# 07_Peripheral_Part.net
KiCad netlist of a schematic drawn in Altium Designer
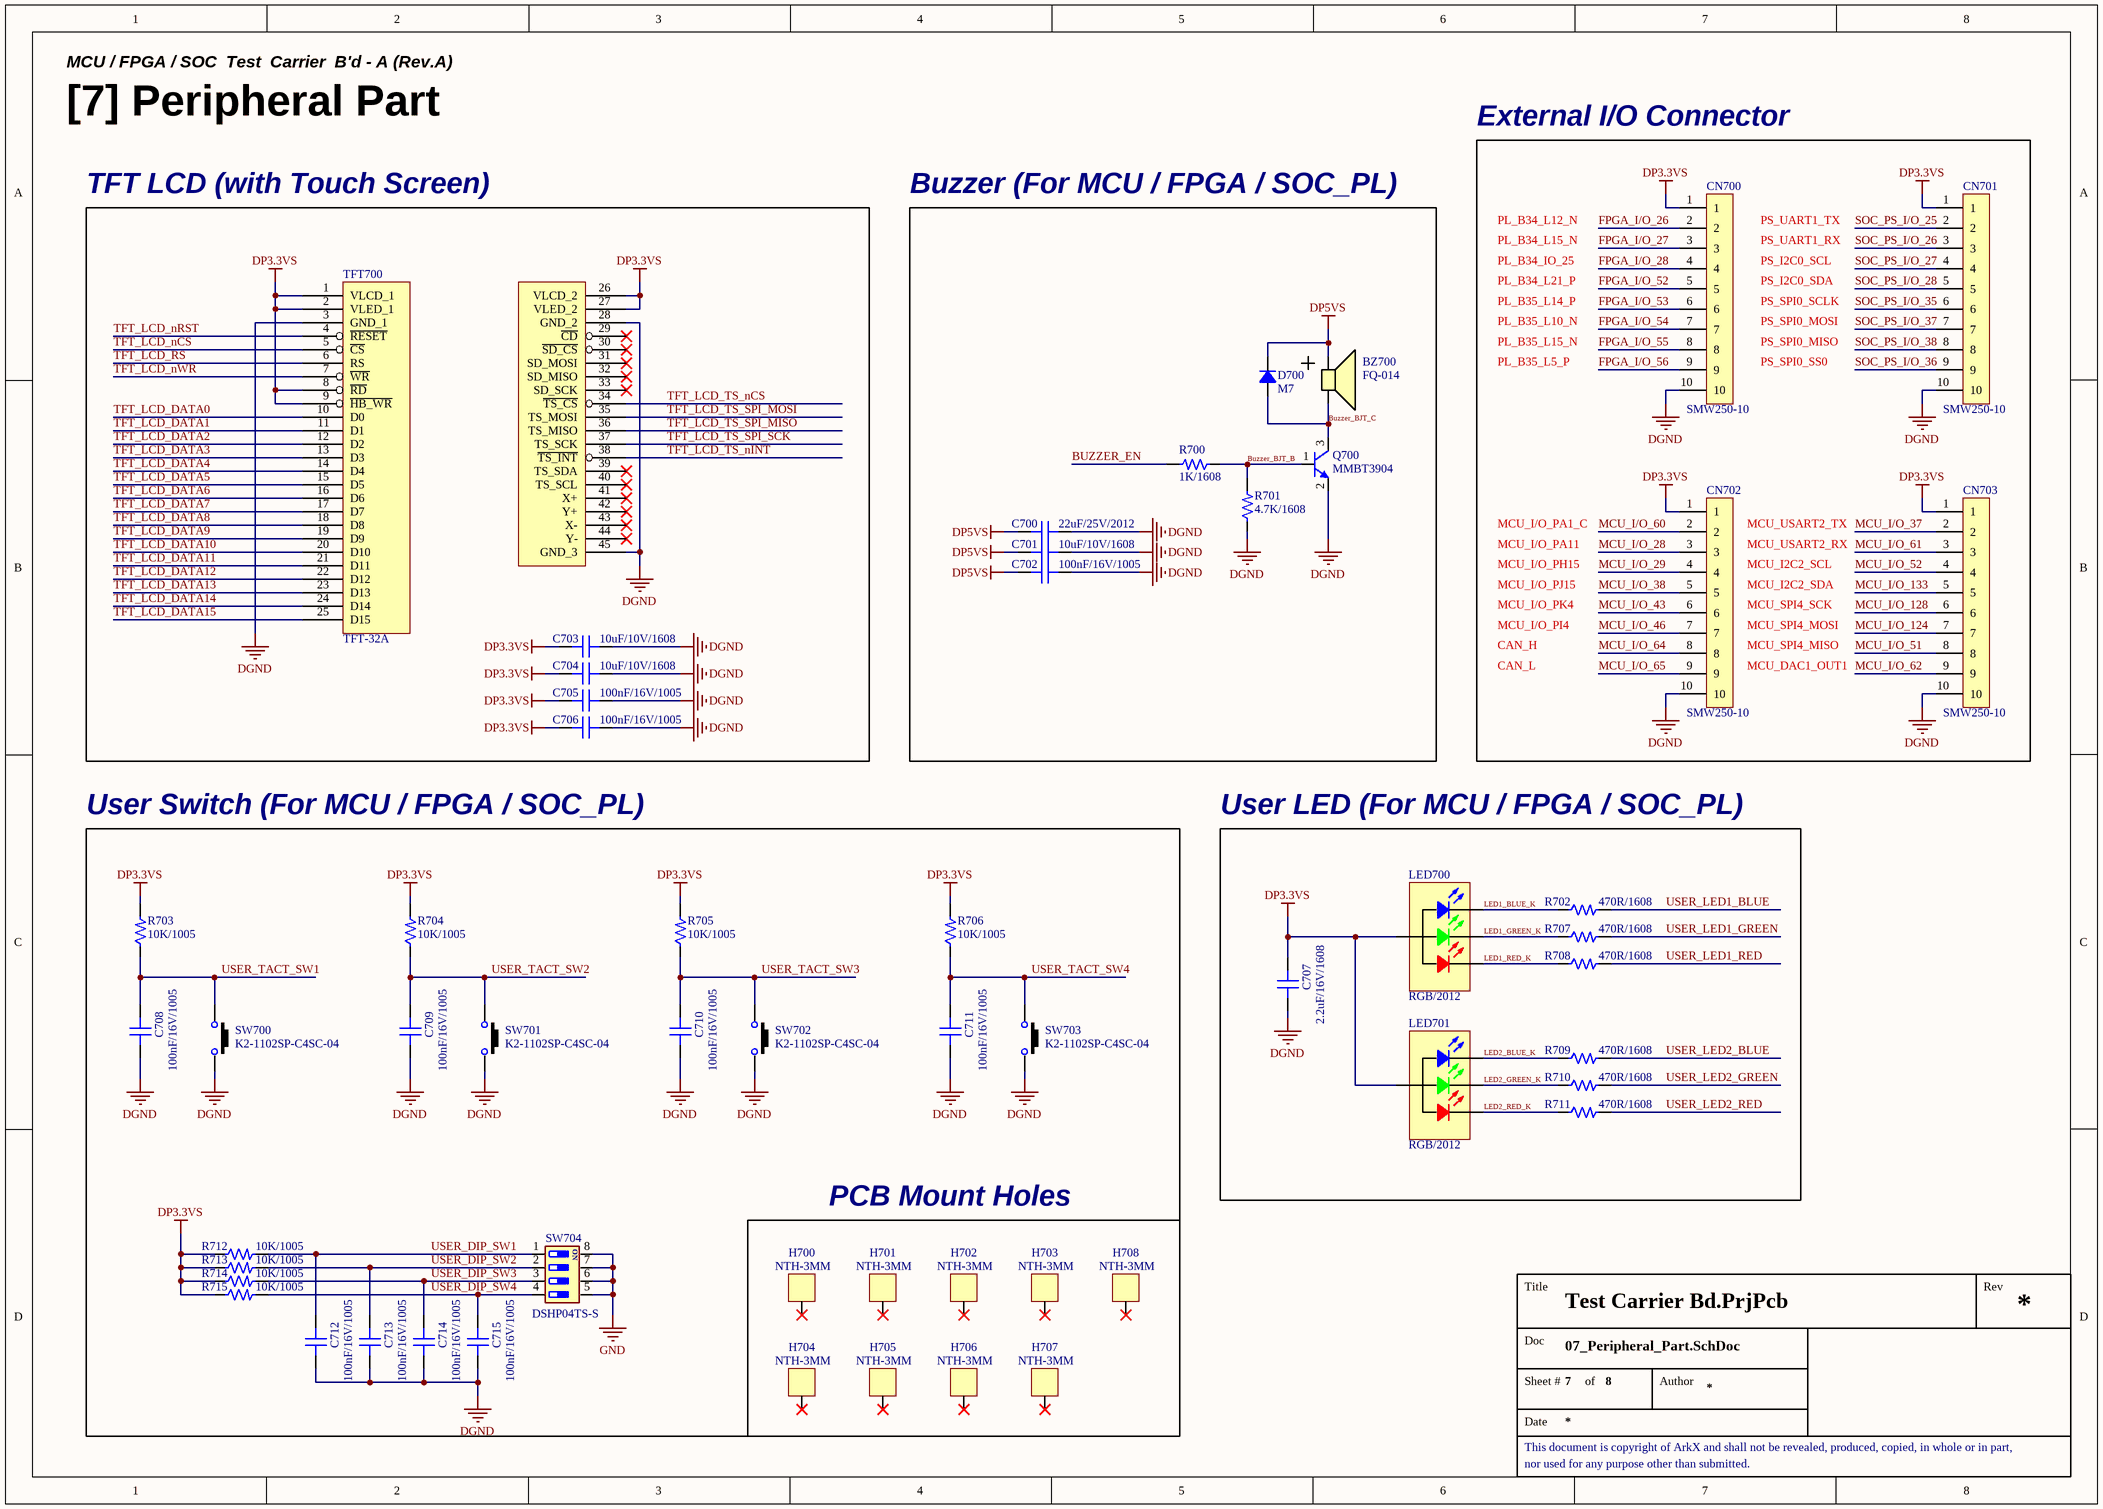
[diagram p0: 07_Peripheral_Part.SchDoc]

(export (version "E")
  (design (tool "Eeschema 10.0.6"))
  (components
    (comp (ref "BZ700")
      (value "FQ-014")
      (footprint "BUZ FQ-013")
      (description "Magnetic Active Buzzer / Rated Voltage: 5V / Size: 9x5.5mm")
      (libsource (lib "Arkx") (part "BZ_FQ-014"))
    )
    (comp (ref "C700")
      (value "22uF/25V/2012")
      (footprint "CAP 2012 (0805_INCH)")
      (description "Ceramic CAP_22uF/25V/2012")
      (fields (field (name "LCSC PART #") "C45783"))
      (libsource (lib "Arkx") (part "CAP_22uF/25V/2012"))
    )
    (comp (ref "C701")
      (value "10uF/10V/1608")
      (footprint "CAP 1608 (0603_INCH)")
      (description "Ceramic CAP_10uF/10V/1608")
      (fields (field (name "LCSC PART #") "C19702"))
      (libsource (lib "Arkx") (part "CAP_10uF/10V/1608"))
    )
    (comp (ref "C702")
      (value "100nF/16V/1005")
      (footprint "CAP 1005 (0402_INCH)")
      (description "Ceramic CAP_100nF/16V/1005")
      (fields (field (name "LCSC PART #") "C1525"))
      (libsource (lib "Arkx") (part "CAP_100nF/16V/1005"))
    )
    (comp (ref "C703")
      (value "10uF/10V/1608")
      (footprint "CAP 1608 (0603_INCH)")
      (description "Ceramic CAP_10uF/10V/1608")
      (fields (field (name "LCSC PART #") "C19702"))
      (libsource (lib "Arkx") (part "CAP_10uF/10V/1608"))
    )
    (comp (ref "C704")
      (value "10uF/10V/1608")
      (footprint "CAP 1608 (0603_INCH)")
      (description "Ceramic CAP_10uF/10V/1608")
      (fields (field (name "LCSC PART #") "C19702"))
      (libsource (lib "Arkx") (part "CAP_10uF/10V/1608"))
    )
    (comp (ref "C705")
      (value "100nF/16V/1005")
      (footprint "CAP 1005 (0402_INCH)")
      (description "Ceramic CAP_100nF/16V/1005")
      (fields (field (name "LCSC PART #") "C1525"))
      (libsource (lib "Arkx") (part "CAP_100nF/16V/1005"))
    )
    (comp (ref "C706")
      (value "100nF/16V/1005")
      (footprint "CAP 1005 (0402_INCH)")
      (description "Ceramic CAP_100nF/16V/1005")
      (fields (field (name "LCSC PART #") "C1525"))
      (libsource (lib "Arkx") (part "CAP_100nF/16V/1005"))
    )
    (comp (ref "C707")
      (value "2.2uF/16V/1608")
      (footprint "CAP 1608 (0603_INCH)")
      (description "Ceramic CAP_2.2uF/16V/1608")
      (fields (field (name "LCSC PART #") "C23630"))
      (libsource (lib "Arkx") (part "CAP_2.2uF/16V/1608"))
    )
    (comp (ref "C708")
      (value "100nF/16V/1005")
      (footprint "CAP 1005 (0402_INCH)")
      (description "Ceramic CAP_100nF/16V/1005")
      (fields (field (name "LCSC PART #") "C1525"))
      (libsource (lib "Arkx") (part "CAP_100nF/16V/1005"))
    )
    (comp (ref "C709")
      (value "100nF/16V/1005")
      (footprint "CAP 1005 (0402_INCH)")
      (description "Ceramic CAP_100nF/16V/1005")
      (fields (field (name "LCSC PART #") "C1525"))
      (libsource (lib "Arkx") (part "CAP_100nF/16V/1005"))
    )
    (comp (ref "C710")
      (value "100nF/16V/1005")
      (footprint "CAP 1005 (0402_INCH)")
      (description "Ceramic CAP_100nF/16V/1005")
      (fields (field (name "LCSC PART #") "C1525"))
      (libsource (lib "Arkx") (part "CAP_100nF/16V/1005"))
    )
    (comp (ref "C711")
      (value "100nF/16V/1005")
      (footprint "CAP 1005 (0402_INCH)")
      (description "Ceramic CAP_100nF/16V/1005")
      (fields (field (name "LCSC PART #") "C1525"))
      (libsource (lib "Arkx") (part "CAP_100nF/16V/1005"))
    )
    (comp (ref "C712")
      (value "100nF/16V/1005")
      (footprint "CAP 1005 (0402_INCH)")
      (description "Ceramic CAP_100nF/16V/1005")
      (fields (field (name "LCSC PART #") "C1525"))
      (libsource (lib "Arkx") (part "CAP_100nF/16V/1005"))
    )
    (comp (ref "C713")
      (value "100nF/16V/1005")
      (footprint "CAP 1005 (0402_INCH)")
      (description "Ceramic CAP_100nF/16V/1005")
      (fields (field (name "LCSC PART #") "C1525"))
      (libsource (lib "Arkx") (part "CAP_100nF/16V/1005"))
    )
    (comp (ref "C714")
      (value "100nF/16V/1005")
      (footprint "CAP 1005 (0402_INCH)")
      (description "Ceramic CAP_100nF/16V/1005")
      (fields (field (name "LCSC PART #") "C1525"))
      (libsource (lib "Arkx") (part "CAP_100nF/16V/1005"))
    )
    (comp (ref "C715")
      (value "100nF/16V/1005")
      (footprint "CAP 1005 (0402_INCH)")
      (description "Ceramic CAP_100nF/16V/1005")
      (fields (field (name "LCSC PART #") "C1525"))
      (libsource (lib "Arkx") (part "CAP_100nF/16V/1005"))
    )
    (comp (ref "CN700")
      (value "SMW250-10")
      (footprint "CON_SMW250-10")
      (description "YEONHO 2.5mm Pitch Vertical Connector 10Pin")
      (libsource (lib "Arkx") (part "CON_SMW250-10"))
    )
    (comp (ref "CN701")
      (value "SMW250-10")
      (footprint "CON_SMW250-10")
      (description "YEONHO 2.5mm Pitch Vertical Connector 10Pin")
      (libsource (lib "Arkx") (part "CON_SMW250-10"))
    )
    (comp (ref "CN702")
      (value "SMW250-10")
      (footprint "CON_SMW250-10")
      (description "YEONHO 2.5mm Pitch Vertical Connector 10Pin")
      (libsource (lib "Arkx") (part "CON_SMW250-10"))
    )
    (comp (ref "CN703")
      (value "SMW250-10")
      (footprint "CON_SMW250-10")
      (description "YEONHO 2.5mm Pitch Vertical Connector 10Pin")
      (libsource (lib "Arkx") (part "CON_SMW250-10"))
    )
    (comp (ref "D700")
      (value "M7")
      (footprint "DIO DO-214AC (SMA)")
      (description "1A 5uA@1kV 1kV 1.1V@1A SMA(DO-214AC)  Diodes - General Purpose ROHS")
      (fields (field (name "LCSC PART #") "C95872"))
      (libsource (lib "Arkx") (part "DIO_M7"))
    )
    (comp (ref "H700")
      (value "NTH-3MM")
      (footprint "HOLE_NTH-3.0MM")
      (description "Non-Through Hole 3mm")
      (libsource (lib "Arkx") (part "HOLE_NTH-3.0MM"))
    )
    (comp (ref "H701")
      (value "NTH-3MM")
      (footprint "HOLE_NTH-3.0MM")
      (description "Non-Through Hole 3mm")
      (libsource (lib "Arkx") (part "HOLE_NTH-3.0MM"))
    )
    (comp (ref "H702")
      (value "NTH-3MM")
      (footprint "HOLE_NTH-3.0MM")
      (description "Non-Through Hole 3mm")
      (libsource (lib "Arkx") (part "HOLE_NTH-3.0MM"))
    )
    (comp (ref "H703")
      (value "NTH-3MM")
      (footprint "HOLE_NTH-3.0MM")
      (description "Non-Through Hole 3mm")
      (libsource (lib "Arkx") (part "HOLE_NTH-3.0MM"))
    )
    (comp (ref "H704")
      (value "NTH-3MM")
      (footprint "HOLE_NTH-3.0MM")
      (description "Non-Through Hole 3mm")
      (libsource (lib "Arkx") (part "HOLE_NTH-3.0MM"))
    )
    (comp (ref "H705")
      (value "NTH-3MM")
      (footprint "HOLE_NTH-3.0MM")
      (description "Non-Through Hole 3mm")
      (libsource (lib "Arkx") (part "HOLE_NTH-3.0MM"))
    )
    (comp (ref "H706")
      (value "NTH-3MM")
      (footprint "HOLE_NTH-3.0MM")
      (description "Non-Through Hole 3mm")
      (libsource (lib "Arkx") (part "HOLE_NTH-3.0MM"))
    )
    (comp (ref "H707")
      (value "NTH-3MM")
      (footprint "HOLE_NTH-3.0MM")
      (description "Non-Through Hole 3mm")
      (libsource (lib "Arkx") (part "HOLE_NTH-3.0MM"))
    )
    (comp (ref "H708")
      (value "NTH-3MM")
      (footprint "HOLE_NTH-3.0MM")
      (description "Non-Through Hole 3mm")
      (libsource (lib "Arkx") (part "HOLE_NTH-3.0MM"))
    )
    (comp (ref "LED700")
      (value "RGB/2012")
      (footprint "LED MHT170RGBCT")
      (fields (field (name "LCSC PART #") "C2962094"))
      (libsource (lib "Arkx") (part "LED_RGB_MHT170RGBCT"))
    )
    (comp (ref "LED701")
      (value "RGB/2012")
      (footprint "LED MHT170RGBCT")
      (fields (field (name "LCSC PART #") "C2962094"))
      (libsource (lib "Arkx") (part "LED_RGB_MHT170RGBCT"))
    )
    (comp (ref "Q700")
      (value "MMBT3904")
      (footprint "SOT 23-3 (DIODES INCORPORATED)")
      (fields (field (name "LCSC PART #") "C20526"))
      (libsource (lib "Arkx") (part "BJT_NPN_MMBT3904"))
    )
    (comp (ref "R700")
      (value "1K/1608")
      (footprint "RES 1608 (0603_inch)")
      (description "RES_1K/1608/0.1W")
      (fields (field (name "LCSC PART #") "C21190"))
      (libsource (lib "Arkx") (part "RES_1K/1608/0.1W"))
    )
    (comp (ref "R701")
      (value "4.7K/1608")
      (footprint "RES 1608 (0603_inch)")
      (description "RES_4.7K/1608/0.1W")
      (fields (field (name "LCSC PART #") "C23162"))
      (libsource (lib "Arkx") (part "RES_4.7K/1608/0.1W"))
    )
    (comp (ref "R702")
      (value "470R/1608")
      (footprint "RES 1608 (0603_inch)")
      (description "RES_470R/1608/0.1W")
      (fields (field (name "LCSC PART #") "C23179"))
      (libsource (lib "Arkx") (part "RES_470R/1608/0.1W"))
    )
    (comp (ref "R703")
      (value "10K/1005")
      (footprint "RES 1005 (0402_inch)")
      (description "RES_10K/1005/62.5mW")
      (fields (field (name "LCSC PART #") "C25744"))
      (libsource (lib "Arkx") (part "RES_10K/1005/62.5mW"))
    )
    (comp (ref "R704")
      (value "10K/1005")
      (footprint "RES 1005 (0402_inch)")
      (description "RES_10K/1005/62.5mW")
      (fields (field (name "LCSC PART #") "C25744"))
      (libsource (lib "Arkx") (part "RES_10K/1005/62.5mW"))
    )
    (comp (ref "R705")
      (value "10K/1005")
      (footprint "RES 1005 (0402_inch)")
      (description "RES_10K/1005/62.5mW")
      (fields (field (name "LCSC PART #") "C25744"))
      (libsource (lib "Arkx") (part "RES_10K/1005/62.5mW"))
    )
    (comp (ref "R706")
      (value "10K/1005")
      (footprint "RES 1005 (0402_inch)")
      (description "RES_10K/1005/62.5mW")
      (fields (field (name "LCSC PART #") "C25744"))
      (libsource (lib "Arkx") (part "RES_10K/1005/62.5mW"))
    )
    (comp (ref "R707")
      (value "470R/1608")
      (footprint "RES 1608 (0603_inch)")
      (description "RES_470R/1608/0.1W")
      (fields (field (name "LCSC PART #") "C23179"))
      (libsource (lib "Arkx") (part "RES_470R/1608/0.1W"))
    )
    (comp (ref "R708")
      (value "470R/1608")
      (footprint "RES 1608 (0603_inch)")
      (description "RES_470R/1608/0.1W")
      (fields (field (name "LCSC PART #") "C23179"))
      (libsource (lib "Arkx") (part "RES_470R/1608/0.1W"))
    )
    (comp (ref "R709")
      (value "470R/1608")
      (footprint "RES 1608 (0603_inch)")
      (description "RES_470R/1608/0.1W")
      (fields (field (name "LCSC PART #") "C23179"))
      (libsource (lib "Arkx") (part "RES_470R/1608/0.1W"))
    )
    (comp (ref "R710")
      (value "470R/1608")
      (footprint "RES 1608 (0603_inch)")
      (description "RES_470R/1608/0.1W")
      (fields (field (name "LCSC PART #") "C23179"))
      (libsource (lib "Arkx") (part "RES_470R/1608/0.1W"))
    )
    (comp (ref "R711")
      (value "470R/1608")
      (footprint "RES 1608 (0603_inch)")
      (description "RES_470R/1608/0.1W")
      (fields (field (name "LCSC PART #") "C23179"))
      (libsource (lib "Arkx") (part "RES_470R/1608/0.1W"))
    )
    (comp (ref "R712")
      (value "10K/1005")
      (footprint "RES 1005 (0402_inch)")
      (description "RES_10K/1005/62.5mW")
      (fields (field (name "LCSC PART #") "C25744"))
      (libsource (lib "Arkx") (part "RES_10K/1005/62.5mW"))
    )
    (comp (ref "R713")
      (value "10K/1005")
      (footprint "RES 1005 (0402_inch)")
      (description "RES_10K/1005/62.5mW")
      (fields (field (name "LCSC PART #") "C25744"))
      (libsource (lib "Arkx") (part "RES_10K/1005/62.5mW"))
    )
    (comp (ref "R714")
      (value "10K/1005")
      (footprint "RES 1005 (0402_inch)")
      (description "RES_10K/1005/62.5mW")
      (fields (field (name "LCSC PART #") "C25744"))
      (libsource (lib "Arkx") (part "RES_10K/1005/62.5mW"))
    )
    (comp (ref "R715")
      (value "10K/1005")
      (footprint "RES 1005 (0402_inch)")
      (description "RES_10K/1005/62.5mW")
      (fields (field (name "LCSC PART #") "C25744"))
      (libsource (lib "Arkx") (part "RES_10K/1005/62.5mW"))
    )
    (comp (ref "SW700")
      (value "K2-1102SP-C4SC-04")
      (footprint "SW K2-1102SP-C4SC-04")
      (fields (field (name "LCSC PART #") "C127509"))
      (libsource (lib "Arkx") (part "SW_K2-1102SP-C4SC-04(2P)"))
    )
    (comp (ref "SW701")
      (value "K2-1102SP-C4SC-04")
      (footprint "SW K2-1102SP-C4SC-04")
      (fields (field (name "LCSC PART #") "C127509"))
      (libsource (lib "Arkx") (part "SW_K2-1102SP-C4SC-04(2P)"))
    )
    (comp (ref "SW702")
      (value "K2-1102SP-C4SC-04")
      (footprint "SW K2-1102SP-C4SC-04")
      (fields (field (name "LCSC PART #") "C127509"))
      (libsource (lib "Arkx") (part "SW_K2-1102SP-C4SC-04(2P)"))
    )
    (comp (ref "SW703")
      (value "K2-1102SP-C4SC-04")
      (footprint "SW K2-1102SP-C4SC-04")
      (fields (field (name "LCSC PART #") "C127509"))
      (libsource (lib "Arkx") (part "SW_K2-1102SP-C4SC-04(2P)"))
    )
    (comp (ref "SW704")
      (value "DSHP04TS-S")
      (footprint "SW_DSHP04TS-S")
      (description "4Bit SPST 24V 25mA Black 3千次 Slide (Standard),凹槽式 SMD-8P,5.4x6.7mm  DIP Switches ROHS")
      (fields (field (name "LCSC PART #") "C319050"))
      (libsource (lib "Arkx") (part "SW_DSHP04TS-S"))
    )
    (comp (ref "TFT700")
      (value "TFT-32A")
      (footprint "LCD_TFT-32A")
      (libsource (lib "Arkx") (part "LCD_TFT-32A"))
    )
  )
  (nets
    (net (code "1") (name "/BUZZER_EN") (class "Default")
      (node (ref "R700") (pin "2") (pinfunction "2_2") (pintype "passive"))
    )
    (net (code "2") (name "/Buzzer_BJT_B") (class "Default")
      (node (ref "Q700") (pin "1") (pinfunction "B_1") (pintype "passive"))
      (node (ref "R700") (pin "1") (pinfunction "1_1") (pintype "passive"))
      (node (ref "R701") (pin "2") (pinfunction "2_2") (pintype "passive"))
    )
    (net (code "3") (name "/Buzzer_BJT_C") (class "Default")
      (node (ref "BZ700") (pin "2") (pinfunction "2_2") (pintype "passive"))
      (node (ref "D700") (pin "1") (pinfunction "1_1") (pintype "passive"))
      (node (ref "Q700") (pin "3") (pinfunction "C_3") (pintype "passive"))
    )
    (net (code "4") (name "/FPGA_I{slash}O_26") (class "Default")
      (node (ref "CN700") (pin "2") (pinfunction "2_2") (pintype "passive"))
    )
    (net (code "5") (name "/FPGA_I{slash}O_27") (class "Default")
      (node (ref "CN700") (pin "3") (pinfunction "3_3") (pintype "passive"))
    )
    (net (code "6") (name "/FPGA_I{slash}O_28") (class "Default")
      (node (ref "CN700") (pin "4") (pinfunction "4_4") (pintype "passive"))
    )
    (net (code "7") (name "/FPGA_I{slash}O_52") (class "Default")
      (node (ref "CN700") (pin "5") (pinfunction "5_5") (pintype "passive"))
    )
    (net (code "8") (name "/FPGA_I{slash}O_53") (class "Default")
      (node (ref "CN700") (pin "6") (pinfunction "6_6") (pintype "passive"))
    )
    (net (code "9") (name "/FPGA_I{slash}O_54") (class "Default")
      (node (ref "CN700") (pin "7") (pinfunction "7_7") (pintype "passive"))
    )
    (net (code "10") (name "/FPGA_I{slash}O_55") (class "Default")
      (node (ref "CN700") (pin "8") (pinfunction "8_8") (pintype "passive"))
    )
    (net (code "11") (name "/FPGA_I{slash}O_56") (class "Default")
      (node (ref "CN700") (pin "9") (pinfunction "9_9") (pintype "passive"))
    )
    (net (code "12") (name "/LED1_BLUE_K") (class "Default")
      (node (ref "LED700") (pin "3") (pinfunction "BLUE_3") (pintype "passive"))
      (node (ref "R702") (pin "1") (pinfunction "1_1") (pintype "passive"))
    )
    (net (code "13") (name "/LED1_GREEN_K") (class "Default")
      (node (ref "LED700") (pin "2") (pinfunction "GREEN_2") (pintype "passive"))
      (node (ref "R707") (pin "1") (pinfunction "1_1") (pintype "passive"))
    )
    (net (code "14") (name "/LED1_RED_K") (class "Default")
      (node (ref "LED700") (pin "1") (pinfunction "RED_1") (pintype "passive"))
      (node (ref "R708") (pin "1") (pinfunction "1_1") (pintype "passive"))
    )
    (net (code "15") (name "/LED2_BLUE_K") (class "Default")
      (node (ref "LED701") (pin "3") (pinfunction "BLUE_3") (pintype "passive"))
      (node (ref "R709") (pin "1") (pinfunction "1_1") (pintype "passive"))
    )
    (net (code "16") (name "/LED2_GREEN_K") (class "Default")
      (node (ref "LED701") (pin "2") (pinfunction "GREEN_2") (pintype "passive"))
      (node (ref "R710") (pin "1") (pinfunction "1_1") (pintype "passive"))
    )
    (net (code "17") (name "/LED2_RED_K") (class "Default")
      (node (ref "LED701") (pin "1") (pinfunction "RED_1") (pintype "passive"))
      (node (ref "R711") (pin "1") (pinfunction "1_1") (pintype "passive"))
    )
    (net (code "18") (name "/MCU_I{slash}O_28") (class "Default")
      (node (ref "CN702") (pin "3") (pinfunction "3_3") (pintype "passive"))
    )
    (net (code "19") (name "/MCU_I{slash}O_29") (class "Default")
      (node (ref "CN702") (pin "4") (pinfunction "4_4") (pintype "passive"))
    )
    (net (code "20") (name "/MCU_I{slash}O_37") (class "Default")
      (node (ref "CN703") (pin "2") (pinfunction "2_2") (pintype "passive"))
    )
    (net (code "21") (name "/MCU_I{slash}O_38") (class "Default")
      (node (ref "CN702") (pin "5") (pinfunction "5_5") (pintype "passive"))
    )
    (net (code "22") (name "/MCU_I{slash}O_43") (class "Default")
      (node (ref "CN702") (pin "6") (pinfunction "6_6") (pintype "passive"))
    )
    (net (code "23") (name "/MCU_I{slash}O_46") (class "Default")
      (node (ref "CN702") (pin "7") (pinfunction "7_7") (pintype "passive"))
    )
    (net (code "24") (name "/MCU_I{slash}O_51") (class "Default")
      (node (ref "CN703") (pin "8") (pinfunction "8_8") (pintype "passive"))
    )
    (net (code "25") (name "/MCU_I{slash}O_52") (class "Default")
      (node (ref "CN703") (pin "4") (pinfunction "4_4") (pintype "passive"))
    )
    (net (code "26") (name "/MCU_I{slash}O_60") (class "Default")
      (node (ref "CN702") (pin "2") (pinfunction "2_2") (pintype "passive"))
    )
    (net (code "27") (name "/MCU_I{slash}O_61") (class "Default")
      (node (ref "CN703") (pin "3") (pinfunction "3_3") (pintype "passive"))
    )
    (net (code "28") (name "/MCU_I{slash}O_62") (class "Default")
      (node (ref "CN703") (pin "9") (pinfunction "9_9") (pintype "passive"))
    )
    (net (code "29") (name "/MCU_I{slash}O_64") (class "Default")
      (node (ref "CN702") (pin "8") (pinfunction "8_8") (pintype "passive"))
    )
    (net (code "30") (name "/MCU_I{slash}O_65") (class "Default")
      (node (ref "CN702") (pin "9") (pinfunction "9_9") (pintype "passive"))
    )
    (net (code "31") (name "/MCU_I{slash}O_124") (class "Default")
      (node (ref "CN703") (pin "7") (pinfunction "7_7") (pintype "passive"))
    )
    (net (code "32") (name "/MCU_I{slash}O_128") (class "Default")
      (node (ref "CN703") (pin "6") (pinfunction "6_6") (pintype "passive"))
    )
    (net (code "33") (name "/MCU_I{slash}O_133") (class "Default")
      (node (ref "CN703") (pin "5") (pinfunction "5_5") (pintype "passive"))
    )
    (net (code "34") (name "/SOC_PS_I{slash}O_25") (class "Default")
      (node (ref "CN701") (pin "2") (pinfunction "2_2") (pintype "passive"))
    )
    (net (code "35") (name "/SOC_PS_I{slash}O_26") (class "Default")
      (node (ref "CN701") (pin "3") (pinfunction "3_3") (pintype "passive"))
    )
    (net (code "36") (name "/SOC_PS_I{slash}O_27") (class "Default")
      (node (ref "CN701") (pin "4") (pinfunction "4_4") (pintype "passive"))
    )
    (net (code "37") (name "/SOC_PS_I{slash}O_28") (class "Default")
      (node (ref "CN701") (pin "5") (pinfunction "5_5") (pintype "passive"))
    )
    (net (code "38") (name "/SOC_PS_I{slash}O_35") (class "Default")
      (node (ref "CN701") (pin "6") (pinfunction "6_6") (pintype "passive"))
    )
    (net (code "39") (name "/SOC_PS_I{slash}O_36") (class "Default")
      (node (ref "CN701") (pin "9") (pinfunction "9_9") (pintype "passive"))
    )
    (net (code "40") (name "/SOC_PS_I{slash}O_37") (class "Default")
      (node (ref "CN701") (pin "7") (pinfunction "7_7") (pintype "passive"))
    )
    (net (code "41") (name "/SOC_PS_I{slash}O_38") (class "Default")
      (node (ref "CN701") (pin "8") (pinfunction "8_8") (pintype "passive"))
    )
    (net (code "42") (name "/TFT_LCD_DATA0") (class "Default")
      (node (ref "TFT700") (pin "10") (pinfunction "D0_10") (pintype "passive"))
    )
    (net (code "43") (name "/TFT_LCD_DATA1") (class "Default")
      (node (ref "TFT700") (pin "11") (pinfunction "D1_11") (pintype "passive"))
    )
    (net (code "44") (name "/TFT_LCD_DATA2") (class "Default")
      (node (ref "TFT700") (pin "12") (pinfunction "D2_12") (pintype "passive"))
    )
    (net (code "45") (name "/TFT_LCD_DATA3") (class "Default")
      (node (ref "TFT700") (pin "13") (pinfunction "D3_13") (pintype "passive"))
    )
    (net (code "46") (name "/TFT_LCD_DATA4") (class "Default")
      (node (ref "TFT700") (pin "14") (pinfunction "D4_14") (pintype "passive"))
    )
    (net (code "47") (name "/TFT_LCD_DATA5") (class "Default")
      (node (ref "TFT700") (pin "15") (pinfunction "D5_15") (pintype "passive"))
    )
    (net (code "48") (name "/TFT_LCD_DATA6") (class "Default")
      (node (ref "TFT700") (pin "16") (pinfunction "D6_16") (pintype "passive"))
    )
    (net (code "49") (name "/TFT_LCD_DATA7") (class "Default")
      (node (ref "TFT700") (pin "17") (pinfunction "D7_17") (pintype "passive"))
    )
    (net (code "50") (name "/TFT_LCD_DATA8") (class "Default")
      (node (ref "TFT700") (pin "18") (pinfunction "D8_18") (pintype "passive"))
    )
    (net (code "51") (name "/TFT_LCD_DATA9") (class "Default")
      (node (ref "TFT700") (pin "19") (pinfunction "D9_19") (pintype "passive"))
    )
    (net (code "52") (name "/TFT_LCD_DATA10") (class "Default")
      (node (ref "TFT700") (pin "20") (pinfunction "D10_20") (pintype "passive"))
    )
    (net (code "53") (name "/TFT_LCD_DATA11") (class "Default")
      (node (ref "TFT700") (pin "21") (pinfunction "D11_21") (pintype "passive"))
    )
    (net (code "54") (name "/TFT_LCD_DATA12") (class "Default")
      (node (ref "TFT700") (pin "22") (pinfunction "D12_22") (pintype "passive"))
    )
    (net (code "55") (name "/TFT_LCD_DATA13") (class "Default")
      (node (ref "TFT700") (pin "23") (pinfunction "D13_23") (pintype "passive"))
    )
    (net (code "56") (name "/TFT_LCD_DATA14") (class "Default")
      (node (ref "TFT700") (pin "24") (pinfunction "D14_24") (pintype "passive"))
    )
    (net (code "57") (name "/TFT_LCD_DATA15") (class "Default")
      (node (ref "TFT700") (pin "25") (pinfunction "D15_25") (pintype "passive"))
    )
    (net (code "58") (name "/TFT_LCD_RS") (class "Default")
      (node (ref "TFT700") (pin "6") (pinfunction "RS_6") (pintype "passive"))
    )
    (net (code "59") (name "/TFT_LCD_TS_SPI_MISO") (class "Default")
      (node (ref "TFT700") (pin "36") (pinfunction "TS_MISO_36") (pintype "passive"))
    )
    (net (code "60") (name "/TFT_LCD_TS_SPI_MOSI") (class "Default")
      (node (ref "TFT700") (pin "35") (pinfunction "TS_MOSI_35") (pintype "passive"))
    )
    (net (code "61") (name "/TFT_LCD_TS_SPI_SCK") (class "Default")
      (node (ref "TFT700") (pin "37") (pinfunction "TS_SCK_37") (pintype "passive"))
    )
    (net (code "62") (name "/TFT_LCD_TS_nCS") (class "Default")
      (node (ref "TFT700") (pin "34") (pinfunction "~{TS_CS}_34") (pintype "passive"))
    )
    (net (code "63") (name "/TFT_LCD_TS_nINT") (class "Default")
      (node (ref "TFT700") (pin "38") (pinfunction "~{TS_INT}_38") (pintype "passive"))
    )
    (net (code "64") (name "/TFT_LCD_nCS") (class "Default")
      (node (ref "TFT700") (pin "5") (pinfunction "~{CS}_5") (pintype "passive"))
    )
    (net (code "65") (name "/TFT_LCD_nRST") (class "Default")
      (node (ref "TFT700") (pin "4") (pinfunction "~{RESET}_4") (pintype "passive"))
    )
    (net (code "66") (name "/TFT_LCD_nWR") (class "Default")
      (node (ref "TFT700") (pin "7") (pinfunction "~{WR}_7") (pintype "passive"))
    )
    (net (code "67") (name "/USER_DIP_SW1") (class "Default")
      (node (ref "C712") (pin "2") (pinfunction "2_2") (pintype "passive"))
      (node (ref "R712") (pin "2") (pinfunction "2_2") (pintype "passive"))
      (node (ref "SW704") (pin "1") (pinfunction "1_1") (pintype "passive"))
    )
    (net (code "68") (name "/USER_DIP_SW2") (class "Default")
      (node (ref "C713") (pin "2") (pinfunction "2_2") (pintype "passive"))
      (node (ref "R713") (pin "2") (pinfunction "2_2") (pintype "passive"))
      (node (ref "SW704") (pin "2") (pinfunction "2_2") (pintype "passive"))
    )
    (net (code "69") (name "/USER_DIP_SW3") (class "Default")
      (node (ref "C714") (pin "2") (pinfunction "2_2") (pintype "passive"))
      (node (ref "R714") (pin "2") (pinfunction "2_2") (pintype "passive"))
      (node (ref "SW704") (pin "3") (pinfunction "3_3") (pintype "passive"))
    )
    (net (code "70") (name "/USER_DIP_SW4") (class "Default")
      (node (ref "C715") (pin "2") (pinfunction "2_2") (pintype "passive"))
      (node (ref "R715") (pin "2") (pinfunction "2_2") (pintype "passive"))
      (node (ref "SW704") (pin "4") (pinfunction "4_4") (pintype "passive"))
    )
    (net (code "71") (name "/USER_LED1_BLUE") (class "Default")
      (node (ref "R702") (pin "2") (pinfunction "2_2") (pintype "passive"))
    )
    (net (code "72") (name "/USER_LED1_GREEN") (class "Default")
      (node (ref "R707") (pin "2") (pinfunction "2_2") (pintype "passive"))
    )
    (net (code "73") (name "/USER_LED1_RED") (class "Default")
      (node (ref "R708") (pin "2") (pinfunction "2_2") (pintype "passive"))
    )
    (net (code "74") (name "/USER_LED2_BLUE") (class "Default")
      (node (ref "R709") (pin "2") (pinfunction "2_2") (pintype "passive"))
    )
    (net (code "75") (name "/USER_LED2_GREEN") (class "Default")
      (node (ref "R710") (pin "2") (pinfunction "2_2") (pintype "passive"))
    )
    (net (code "76") (name "/USER_LED2_RED") (class "Default")
      (node (ref "R711") (pin "2") (pinfunction "2_2") (pintype "passive"))
    )
    (net (code "77") (name "/USER_TACT_SW1") (class "Default")
      (node (ref "C708") (pin "2") (pinfunction "2_2") (pintype "passive"))
      (node (ref "R703") (pin "1") (pinfunction "1_1") (pintype "passive"))
      (node (ref "SW700") (pin "1") (pinfunction "1_1") (pintype "passive"))
    )
    (net (code "78") (name "/USER_TACT_SW2") (class "Default")
      (node (ref "C709") (pin "2") (pinfunction "2_2") (pintype "passive"))
      (node (ref "R704") (pin "1") (pinfunction "1_1") (pintype "passive"))
      (node (ref "SW701") (pin "1") (pinfunction "1_1") (pintype "passive"))
    )
    (net (code "79") (name "/USER_TACT_SW3") (class "Default")
      (node (ref "C710") (pin "2") (pinfunction "2_2") (pintype "passive"))
      (node (ref "R705") (pin "1") (pinfunction "1_1") (pintype "passive"))
      (node (ref "SW702") (pin "1") (pinfunction "1_1") (pintype "passive"))
    )
    (net (code "80") (name "/USER_TACT_SW4") (class "Default")
      (node (ref "C711") (pin "2") (pinfunction "2_2") (pintype "passive"))
      (node (ref "R706") (pin "1") (pinfunction "1_1") (pintype "passive"))
      (node (ref "SW703") (pin "1") (pinfunction "1_1") (pintype "passive"))
    )
    (net (code "81") (name "DGND") (class "Default")
      (node (ref "C700") (pin "2") (pinfunction "2_2") (pintype "passive"))
      (node (ref "C701") (pin "1") (pinfunction "1_1") (pintype "passive"))
      (node (ref "C702") (pin "1") (pinfunction "1_1") (pintype "passive"))
      (node (ref "C703") (pin "1") (pinfunction "1_1") (pintype "passive"))
      (node (ref "C704") (pin "1") (pinfunction "1_1") (pintype "passive"))
      (node (ref "C705") (pin "1") (pinfunction "1_1") (pintype "passive"))
      (node (ref "C706") (pin "1") (pinfunction "1_1") (pintype "passive"))
      (node (ref "C707") (pin "2") (pinfunction "2_2") (pintype "passive"))
      (node (ref "C708") (pin "1") (pinfunction "1_1") (pintype "passive"))
      (node (ref "C709") (pin "1") (pinfunction "1_1") (pintype "passive"))
      (node (ref "C710") (pin "1") (pinfunction "1_1") (pintype "passive"))
      (node (ref "C711") (pin "1") (pinfunction "1_1") (pintype "passive"))
      (node (ref "C712") (pin "1") (pinfunction "1_1") (pintype "passive"))
      (node (ref "C713") (pin "1") (pinfunction "1_1") (pintype "passive"))
      (node (ref "C714") (pin "1") (pinfunction "1_1") (pintype "passive"))
      (node (ref "C715") (pin "1") (pinfunction "1_1") (pintype "passive"))
      (node (ref "CN700") (pin "10") (pinfunction "10_10") (pintype "passive"))
      (node (ref "CN701") (pin "10") (pinfunction "10_10") (pintype "passive"))
      (node (ref "CN702") (pin "10") (pinfunction "10_10") (pintype "passive"))
      (node (ref "CN703") (pin "10") (pinfunction "10_10") (pintype "passive"))
      (node (ref "Q700") (pin "2") (pinfunction "E_2") (pintype "passive"))
      (node (ref "R701") (pin "1") (pinfunction "1_1") (pintype "passive"))
      (node (ref "SW700") (pin "3") (pinfunction "3_3") (pintype "passive"))
      (node (ref "SW701") (pin "3") (pinfunction "3_3") (pintype "passive"))
      (node (ref "SW702") (pin "3") (pinfunction "3_3") (pintype "passive"))
      (node (ref "SW703") (pin "3") (pinfunction "3_3") (pintype "passive"))
      (node (ref "TFT700") (pin "28") (pinfunction "GND_2_28") (pintype "power_in"))
      (node (ref "TFT700") (pin "3") (pinfunction "GND_1_3") (pintype "power_in"))
      (node (ref "TFT700") (pin "45") (pinfunction "GND_3_45") (pintype "power_in"))
    )
    (net (code "82") (name "DP3.3VS") (class "Default")
      (node (ref "C703") (pin "2") (pinfunction "2_2") (pintype "passive"))
      (node (ref "C704") (pin "2") (pinfunction "2_2") (pintype "passive"))
      (node (ref "C705") (pin "2") (pinfunction "2_2") (pintype "passive"))
      (node (ref "C706") (pin "2") (pinfunction "2_2") (pintype "passive"))
      (node (ref "C707") (pin "1") (pinfunction "1_1") (pintype "passive"))
      (node (ref "CN700") (pin "1") (pinfunction "1_1") (pintype "passive"))
      (node (ref "CN701") (pin "1") (pinfunction "1_1") (pintype "passive"))
      (node (ref "CN702") (pin "1") (pinfunction "1_1") (pintype "passive"))
      (node (ref "CN703") (pin "1") (pinfunction "1_1") (pintype "passive"))
      (node (ref "LED700") (pin "4") (pinfunction "Common_Anode_4") (pintype "passive"))
      (node (ref "LED701") (pin "4") (pinfunction "Common_Anode_4") (pintype "passive"))
      (node (ref "R703") (pin "2") (pinfunction "2_2") (pintype "passive"))
      (node (ref "R704") (pin "2") (pinfunction "2_2") (pintype "passive"))
      (node (ref "R705") (pin "2") (pinfunction "2_2") (pintype "passive"))
      (node (ref "R706") (pin "2") (pinfunction "2_2") (pintype "passive"))
      (node (ref "R712") (pin "1") (pinfunction "1_1") (pintype "passive"))
      (node (ref "R713") (pin "1") (pinfunction "1_1") (pintype "passive"))
      (node (ref "R714") (pin "1") (pinfunction "1_1") (pintype "passive"))
      (node (ref "R715") (pin "1") (pinfunction "1_1") (pintype "passive"))
      (node (ref "TFT700") (pin "1") (pinfunction "VLCD_1_1") (pintype "power_in"))
      (node (ref "TFT700") (pin "2") (pinfunction "VLED_1_2") (pintype "power_in"))
      (node (ref "TFT700") (pin "26") (pinfunction "VLCD_2_26") (pintype "power_in"))
      (node (ref "TFT700") (pin "27") (pinfunction "VLED_2_27") (pintype "power_in"))
      (node (ref "TFT700") (pin "8") (pinfunction "~{RD}_8") (pintype "passive"))
      (node (ref "TFT700") (pin "9") (pinfunction "~{HB_WR}_9") (pintype "passive"))
    )
    (net (code "83") (name "DP5VS") (class "Default")
      (node (ref "BZ700") (pin "1") (pinfunction "1_1") (pintype "passive"))
      (node (ref "C700") (pin "1") (pinfunction "1_1") (pintype "passive"))
      (node (ref "C701") (pin "2") (pinfunction "2_2") (pintype "passive"))
      (node (ref "C702") (pin "2") (pinfunction "2_2") (pintype "passive"))
      (node (ref "D700") (pin "2") (pinfunction "2_2") (pintype "passive"))
    )
    (net (code "84") (name "GND") (class "Default")
      (node (ref "SW704") (pin "5") (pinfunction "5_5") (pintype "passive"))
      (node (ref "SW704") (pin "6") (pinfunction "6_6") (pintype "passive"))
      (node (ref "SW704") (pin "7") (pinfunction "7_7") (pintype "passive"))
      (node (ref "SW704") (pin "8") (pinfunction "8_8") (pintype "passive"))
    )
    (net (code "85") (name "unconnected-(H700-Pad1)") (class "Default")
      (node (ref "H700") (pin "1") (pinfunction "1_1") (pintype "passive+no_connect"))
    )
    (net (code "86") (name "unconnected-(H701-Pad1)") (class "Default")
      (node (ref "H701") (pin "1") (pinfunction "1_1") (pintype "passive+no_connect"))
    )
    (net (code "87") (name "unconnected-(H702-Pad1)") (class "Default")
      (node (ref "H702") (pin "1") (pinfunction "1_1") (pintype "passive+no_connect"))
    )
    (net (code "88") (name "unconnected-(H703-Pad1)") (class "Default")
      (node (ref "H703") (pin "1") (pinfunction "1_1") (pintype "passive+no_connect"))
    )
    (net (code "89") (name "unconnected-(H704-Pad1)") (class "Default")
      (node (ref "H704") (pin "1") (pinfunction "1_1") (pintype "passive+no_connect"))
    )
    (net (code "90") (name "unconnected-(H705-Pad1)") (class "Default")
      (node (ref "H705") (pin "1") (pinfunction "1_1") (pintype "passive+no_connect"))
    )
    (net (code "91") (name "unconnected-(H706-Pad1)") (class "Default")
      (node (ref "H706") (pin "1") (pinfunction "1_1") (pintype "passive+no_connect"))
    )
    (net (code "92") (name "unconnected-(H707-Pad1)") (class "Default")
      (node (ref "H707") (pin "1") (pinfunction "1_1") (pintype "passive+no_connect"))
    )
    (net (code "93") (name "unconnected-(H708-Pad1)") (class "Default")
      (node (ref "H708") (pin "1") (pinfunction "1_1") (pintype "passive+no_connect"))
    )
    (net (code "94") (name "unconnected-(TFT700-SD_MISO-Pad32)") (class "Default")
      (node (ref "TFT700") (pin "32") (pinfunction "SD_MISO_32") (pintype "passive+no_connect"))
    )
    (net (code "95") (name "unconnected-(TFT700-SD_MOSI-Pad31)") (class "Default")
      (node (ref "TFT700") (pin "31") (pinfunction "SD_MOSI_31") (pintype "passive+no_connect"))
    )
    (net (code "96") (name "unconnected-(TFT700-SD_SCK-Pad33)") (class "Default")
      (node (ref "TFT700") (pin "33") (pinfunction "SD_SCK_33") (pintype "passive+no_connect"))
    )
    (net (code "97") (name "unconnected-(TFT700-TS_SCL-Pad40)") (class "Default")
      (node (ref "TFT700") (pin "40") (pinfunction "TS_SCL_40") (pintype "passive+no_connect"))
    )
    (net (code "98") (name "unconnected-(TFT700-TS_SDA-Pad39)") (class "Default")
      (node (ref "TFT700") (pin "39") (pinfunction "TS_SDA_39") (pintype "passive+no_connect"))
    )
    (net (code "99") (name "unconnected-(TFT700-X+-Pad41)") (class "Default")
      (node (ref "TFT700") (pin "41") (pinfunction "X+_41") (pintype "passive+no_connect"))
    )
    (net (code "100") (name "unconnected-(TFT700-X--Pad43)") (class "Default")
      (node (ref "TFT700") (pin "43") (pinfunction "X-_43") (pintype "passive+no_connect"))
    )
    (net (code "101") (name "unconnected-(TFT700-Y+-Pad42)") (class "Default")
      (node (ref "TFT700") (pin "42") (pinfunction "Y+_42") (pintype "passive+no_connect"))
    )
    (net (code "102") (name "unconnected-(TFT700-Y--Pad44)") (class "Default")
      (node (ref "TFT700") (pin "44") (pinfunction "Y-_44") (pintype "passive+no_connect"))
    )
    (net (code "103") (name "unconnected-(TFT700-~{CD}-Pad29)") (class "Default")
      (node (ref "TFT700") (pin "29") (pinfunction "~{CD}_29") (pintype "passive+no_connect"))
    )
    (net (code "104") (name "unconnected-(TFT700-~{SD_CS}-Pad30)") (class "Default")
      (node (ref "TFT700") (pin "30") (pinfunction "~{SD_CS}_30") (pintype "passive+no_connect"))
    )
  )
)
